# passive_balancing.net
KiCad netlist of a schematic drawn in Altium Designer
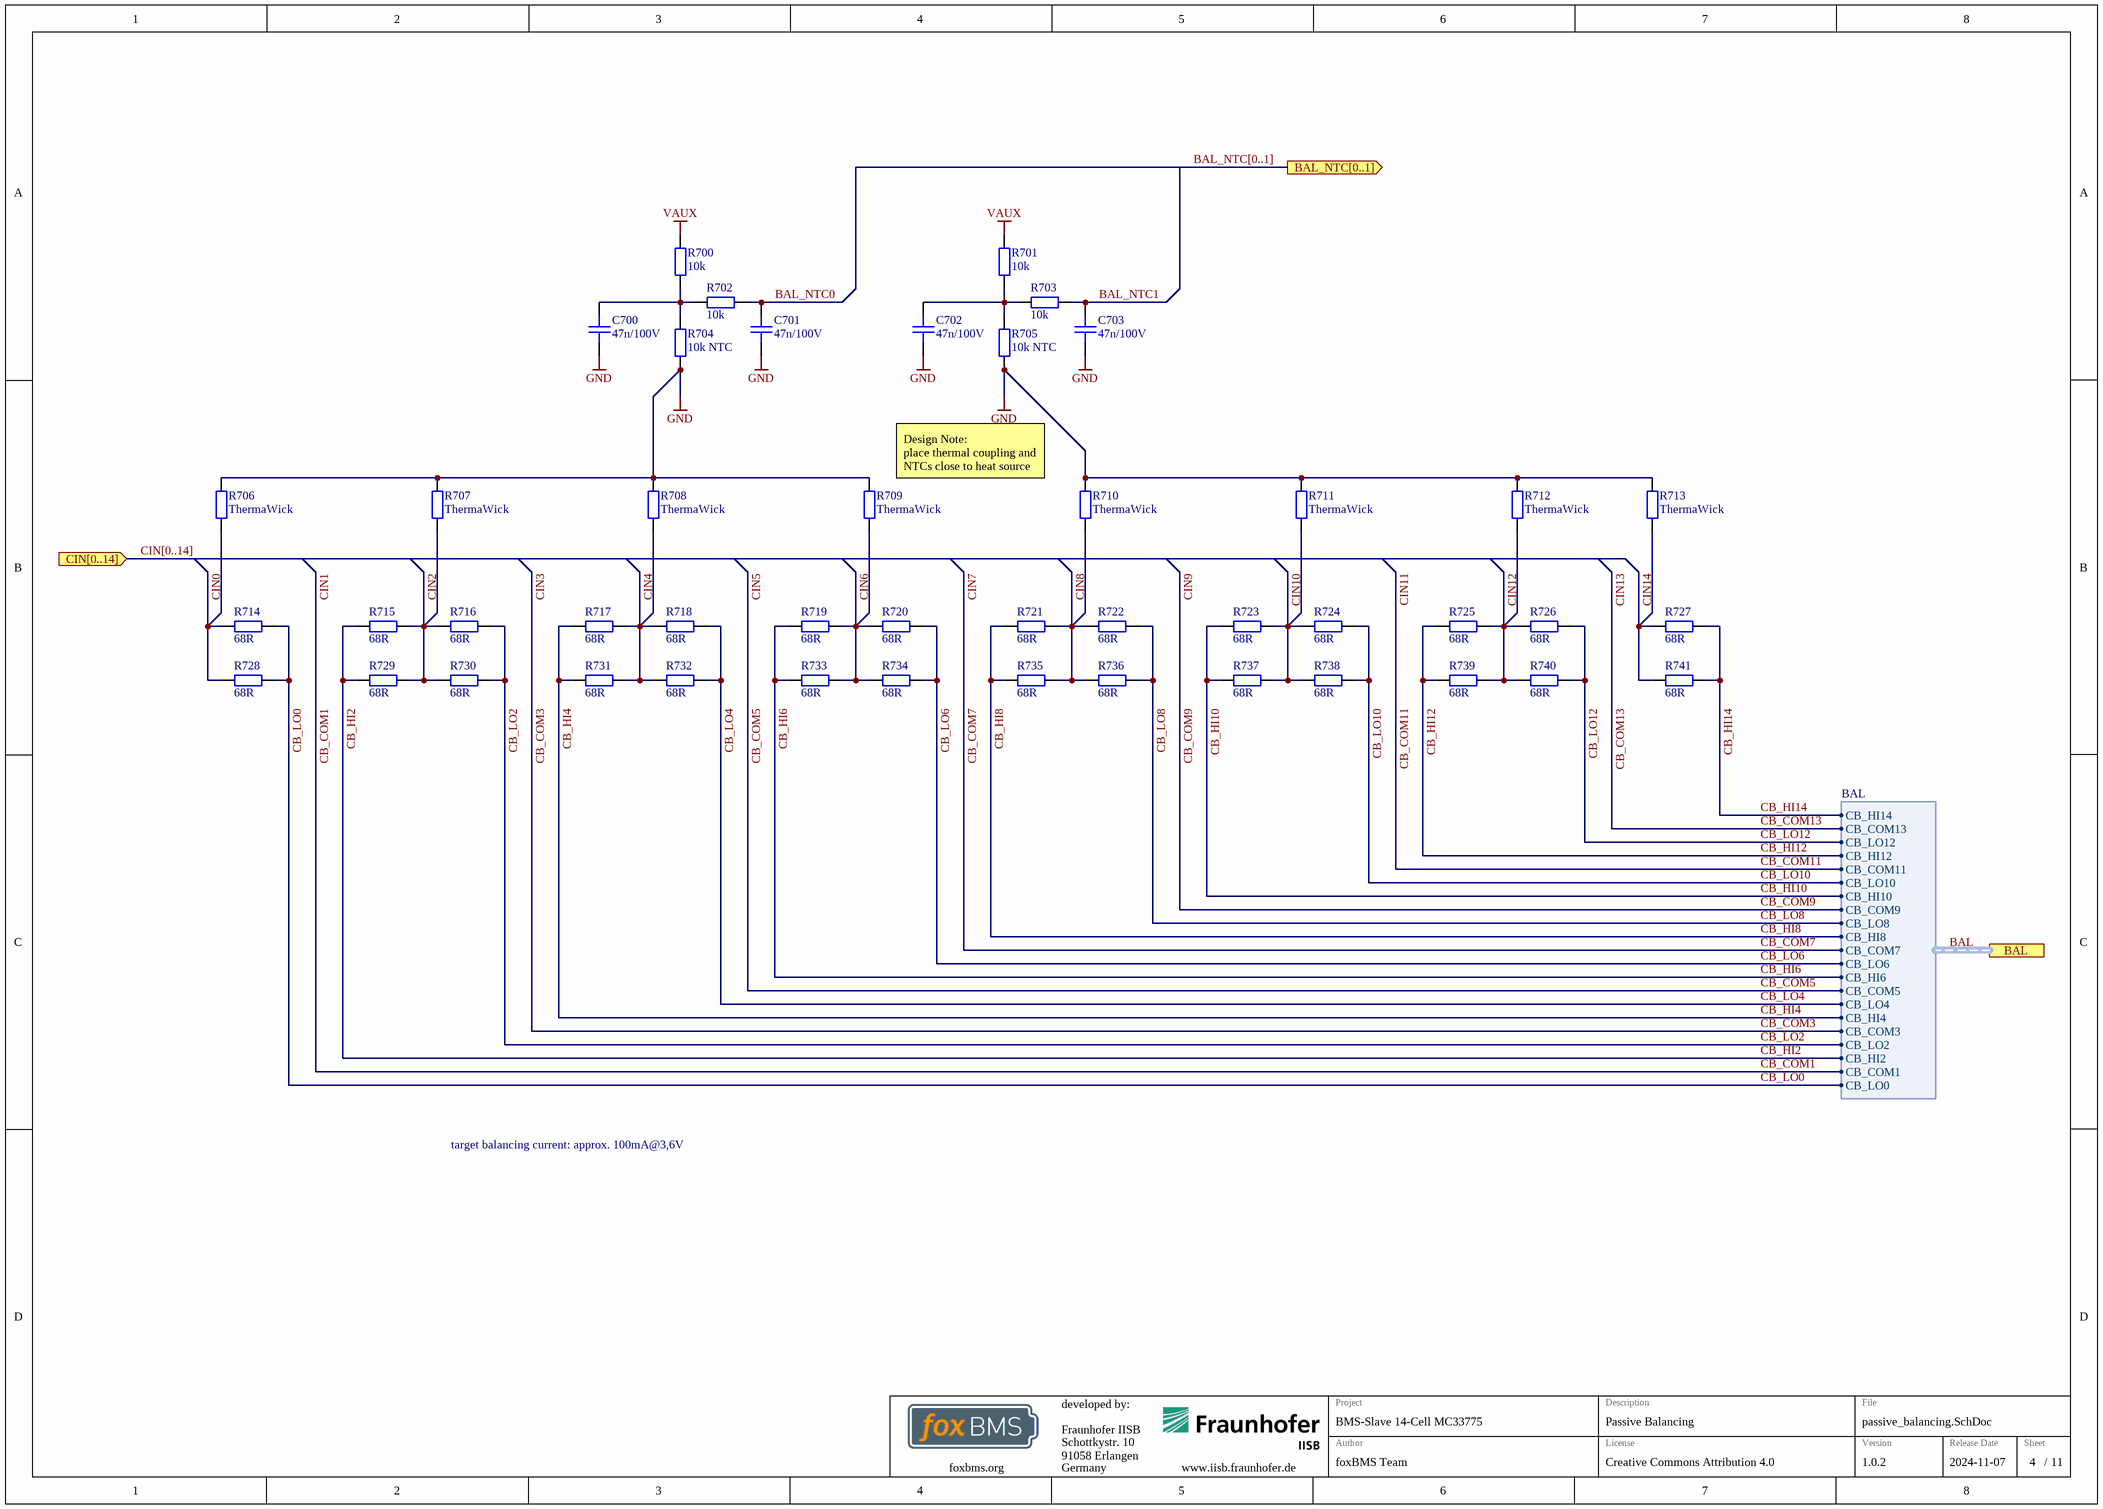
[diagram p0: passive_balancing.SchDoc]

(export (version "E")
  (design (tool "Eeschema 10.0.6"))
  (components
    (comp (ref "C700")
      (value "47n/100V")
      (footprint "CAPC1608X08N")
      (description "MLCC")
      (fields (field (name "PART NUMBER") "gen_C_ceramic_47n_100V_X7R_0603"))
      (libsource (lib "OE750") (part "C"))
    )
    (comp (ref "C701")
      (value "47n/100V")
      (footprint "CAPC1608X08N")
      (description "MLCC")
      (fields (field (name "PART NUMBER") "gen_C_ceramic_47n_100V_X7R_0603"))
      (libsource (lib "OE750") (part "C"))
    )
    (comp (ref "C702")
      (value "47n/100V")
      (footprint "CAPC1608X08N")
      (description "MLCC")
      (fields (field (name "PART NUMBER") "gen_C_ceramic_47n_100V_X7R_0603"))
      (libsource (lib "OE750") (part "C"))
    )
    (comp (ref "C703")
      (value "47n/100V")
      (footprint "CAPC1608X08N")
      (description "MLCC")
      (fields (field (name "PART NUMBER") "gen_C_ceramic_47n_100V_X7R_0603"))
      (libsource (lib "OE750") (part "C"))
    )
    (comp (ref "R700")
      (value "10k")
      (footprint "RESC1608X05N")
      (description "SMD Resistor 10k 0603")
      (fields (field (name "PART NUMBER") "gen_R_10k_0603") (field (name "TOLERANCE") "1%"))
      (libsource (lib "OE750") (part "R"))
    )
    (comp (ref "R701")
      (value "10k")
      (footprint "RESC1608X05N")
      (description "SMD Resistor 10k 0603")
      (fields (field (name "PART NUMBER") "gen_R_10k_0603") (field (name "TOLERANCE") "1%"))
      (libsource (lib "OE750") (part "R"))
    )
    (comp (ref "R702")
      (value "10k")
      (footprint "RESC1608X05N")
      (description "SMD Resistor 10k 0603")
      (fields (field (name "PART NUMBER") "gen_R_10k_0603") (field (name "TOLERANCE") "1%"))
      (libsource (lib "OE750") (part "R"))
    )
    (comp (ref "R703")
      (value "10k")
      (footprint "RESC1608X05N")
      (description "SMD Resistor 10k 0603")
      (fields (field (name "PART NUMBER") "gen_R_10k_0603") (field (name "TOLERANCE") "1%"))
      (libsource (lib "OE750") (part "R"))
    )
    (comp (ref "R704")
      (value "10k NTC")
      (footprint "RESC1005X04N")
      (description "SMD Resistor 10k NTC 0402")
      (fields (field (name "PART NUMBER") "gen_R_10k_NTC_0402") (field (name "POWER") "0.150W"))
      (libsource (lib "OE750") (part "R"))
    )
    (comp (ref "R705")
      (value "10k NTC")
      (footprint "RESC1005X04N")
      (description "SMD Resistor 10k NTC 0402")
      (fields (field (name "PART NUMBER") "gen_R_10k_NTC_0402") (field (name "POWER") "0.150W"))
      (libsource (lib "OE750") (part "R"))
    )
    (comp (ref "R706")
      (value "ThermaWick")
      (footprint "Vishay_THJP_0603")
      (description "ThermaWick thermal coupling 0603")
      (fields (field (name "PART NUMBER") "Vishay_THJP_0603"))
      (libsource (lib "OE750") (part "R"))
    )
    (comp (ref "R707")
      (value "ThermaWick")
      (footprint "Vishay_THJP_0603")
      (description "ThermaWick thermal coupling 0603")
      (fields (field (name "PART NUMBER") "Vishay_THJP_0603"))
      (libsource (lib "OE750") (part "R"))
    )
    (comp (ref "R708")
      (value "ThermaWick")
      (footprint "Vishay_THJP_0603")
      (description "ThermaWick thermal coupling 0603")
      (fields (field (name "PART NUMBER") "Vishay_THJP_0603"))
      (libsource (lib "OE750") (part "R"))
    )
    (comp (ref "R709")
      (value "ThermaWick")
      (footprint "Vishay_THJP_0603")
      (description "ThermaWick thermal coupling 0603")
      (fields (field (name "PART NUMBER") "Vishay_THJP_0603"))
      (libsource (lib "OE750") (part "R"))
    )
    (comp (ref "R710")
      (value "ThermaWick")
      (footprint "Vishay_THJP_0603")
      (description "ThermaWick thermal coupling 0603")
      (fields (field (name "PART NUMBER") "Vishay_THJP_0603"))
      (libsource (lib "OE750") (part "R"))
    )
    (comp (ref "R711")
      (value "ThermaWick")
      (footprint "Vishay_THJP_0603")
      (description "ThermaWick thermal coupling 0603")
      (fields (field (name "PART NUMBER") "Vishay_THJP_0603"))
      (libsource (lib "OE750") (part "R"))
    )
    (comp (ref "R712")
      (value "ThermaWick")
      (footprint "Vishay_THJP_0603")
      (description "ThermaWick thermal coupling 0603")
      (fields (field (name "PART NUMBER") "Vishay_THJP_0603"))
      (libsource (lib "OE750") (part "R"))
    )
    (comp (ref "R713")
      (value "ThermaWick")
      (footprint "Vishay_THJP_0603")
      (description "ThermaWick thermal coupling 0603")
      (fields (field (name "PART NUMBER") "Vishay_THJP_0603"))
      (libsource (lib "OE750") (part "R"))
    )
    (comp (ref "R714")
      (value "68R")
      (footprint "RESC5025X07N")
      (description "SMD Resistor 68R 2010")
      (fields (field (name "PART NUMBER") "gen_R_68R_2010") (field (name "TOLERANCE") "1%"))
      (libsource (lib "OE750") (part "R"))
    )
    (comp (ref "R715")
      (value "68R")
      (footprint "RESC5025X07N")
      (description "SMD Resistor 68R 2010")
      (fields (field (name "PART NUMBER") "gen_R_68R_2010") (field (name "TOLERANCE") "1%"))
      (libsource (lib "OE750") (part "R"))
    )
    (comp (ref "R716")
      (value "68R")
      (footprint "RESC5025X07N")
      (description "SMD Resistor 68R 2010")
      (fields (field (name "PART NUMBER") "gen_R_68R_2010") (field (name "TOLERANCE") "1%"))
      (libsource (lib "OE750") (part "R"))
    )
    (comp (ref "R717")
      (value "68R")
      (footprint "RESC5025X07N")
      (description "SMD Resistor 68R 2010")
      (fields (field (name "PART NUMBER") "gen_R_68R_2010") (field (name "TOLERANCE") "1%"))
      (libsource (lib "OE750") (part "R"))
    )
    (comp (ref "R718")
      (value "68R")
      (footprint "RESC5025X07N")
      (description "SMD Resistor 68R 2010")
      (fields (field (name "PART NUMBER") "gen_R_68R_2010") (field (name "TOLERANCE") "1%"))
      (libsource (lib "OE750") (part "R"))
    )
    (comp (ref "R719")
      (value "68R")
      (footprint "RESC5025X07N")
      (description "SMD Resistor 68R 2010")
      (fields (field (name "PART NUMBER") "gen_R_68R_2010") (field (name "TOLERANCE") "1%"))
      (libsource (lib "OE750") (part "R"))
    )
    (comp (ref "R720")
      (value "68R")
      (footprint "RESC5025X07N")
      (description "SMD Resistor 68R 2010")
      (fields (field (name "PART NUMBER") "gen_R_68R_2010") (field (name "TOLERANCE") "1%"))
      (libsource (lib "OE750") (part "R"))
    )
    (comp (ref "R721")
      (value "68R")
      (footprint "RESC5025X07N")
      (description "SMD Resistor 68R 2010")
      (fields (field (name "PART NUMBER") "gen_R_68R_2010") (field (name "TOLERANCE") "1%"))
      (libsource (lib "OE750") (part "R"))
    )
    (comp (ref "R722")
      (value "68R")
      (footprint "RESC5025X07N")
      (description "SMD Resistor 68R 2010")
      (fields (field (name "PART NUMBER") "gen_R_68R_2010") (field (name "TOLERANCE") "1%"))
      (libsource (lib "OE750") (part "R"))
    )
    (comp (ref "R723")
      (value "68R")
      (footprint "RESC5025X07N")
      (description "SMD Resistor 68R 2010")
      (fields (field (name "PART NUMBER") "gen_R_68R_2010") (field (name "TOLERANCE") "1%"))
      (libsource (lib "OE750") (part "R"))
    )
    (comp (ref "R724")
      (value "68R")
      (footprint "RESC5025X07N")
      (description "SMD Resistor 68R 2010")
      (fields (field (name "PART NUMBER") "gen_R_68R_2010") (field (name "TOLERANCE") "1%"))
      (libsource (lib "OE750") (part "R"))
    )
    (comp (ref "R725")
      (value "68R")
      (footprint "RESC5025X07N")
      (description "SMD Resistor 68R 2010")
      (fields (field (name "PART NUMBER") "gen_R_68R_2010") (field (name "TOLERANCE") "1%"))
      (libsource (lib "OE750") (part "R"))
    )
    (comp (ref "R726")
      (value "68R")
      (footprint "RESC5025X07N")
      (description "SMD Resistor 68R 2010")
      (fields (field (name "PART NUMBER") "gen_R_68R_2010") (field (name "TOLERANCE") "1%"))
      (libsource (lib "OE750") (part "R"))
    )
    (comp (ref "R727")
      (value "68R")
      (footprint "RESC5025X07N")
      (description "SMD Resistor 68R 2010")
      (fields (field (name "PART NUMBER") "gen_R_68R_2010") (field (name "TOLERANCE") "1%"))
      (libsource (lib "OE750") (part "R"))
    )
    (comp (ref "R728")
      (value "68R")
      (footprint "RESC5025X07N")
      (description "SMD Resistor 68R 2010")
      (fields (field (name "PART NUMBER") "gen_R_68R_2010") (field (name "TOLERANCE") "1%"))
      (libsource (lib "OE750") (part "R"))
    )
    (comp (ref "R729")
      (value "68R")
      (footprint "RESC5025X07N")
      (description "SMD Resistor 68R 2010")
      (fields (field (name "PART NUMBER") "gen_R_68R_2010") (field (name "TOLERANCE") "1%"))
      (libsource (lib "OE750") (part "R"))
    )
    (comp (ref "R730")
      (value "68R")
      (footprint "RESC5025X07N")
      (description "SMD Resistor 68R 2010")
      (fields (field (name "PART NUMBER") "gen_R_68R_2010") (field (name "TOLERANCE") "1%"))
      (libsource (lib "OE750") (part "R"))
    )
    (comp (ref "R731")
      (value "68R")
      (footprint "RESC5025X07N")
      (description "SMD Resistor 68R 2010")
      (fields (field (name "PART NUMBER") "gen_R_68R_2010") (field (name "TOLERANCE") "1%"))
      (libsource (lib "OE750") (part "R"))
    )
    (comp (ref "R732")
      (value "68R")
      (footprint "RESC5025X07N")
      (description "SMD Resistor 68R 2010")
      (fields (field (name "PART NUMBER") "gen_R_68R_2010") (field (name "TOLERANCE") "1%"))
      (libsource (lib "OE750") (part "R"))
    )
    (comp (ref "R733")
      (value "68R")
      (footprint "RESC5025X07N")
      (description "SMD Resistor 68R 2010")
      (fields (field (name "PART NUMBER") "gen_R_68R_2010") (field (name "TOLERANCE") "1%"))
      (libsource (lib "OE750") (part "R"))
    )
    (comp (ref "R734")
      (value "68R")
      (footprint "RESC5025X07N")
      (description "SMD Resistor 68R 2010")
      (fields (field (name "PART NUMBER") "gen_R_68R_2010") (field (name "TOLERANCE") "1%"))
      (libsource (lib "OE750") (part "R"))
    )
    (comp (ref "R735")
      (value "68R")
      (footprint "RESC5025X07N")
      (description "SMD Resistor 68R 2010")
      (fields (field (name "PART NUMBER") "gen_R_68R_2010") (field (name "TOLERANCE") "1%"))
      (libsource (lib "OE750") (part "R"))
    )
    (comp (ref "R736")
      (value "68R")
      (footprint "RESC5025X07N")
      (description "SMD Resistor 68R 2010")
      (fields (field (name "PART NUMBER") "gen_R_68R_2010") (field (name "TOLERANCE") "1%"))
      (libsource (lib "OE750") (part "R"))
    )
    (comp (ref "R737")
      (value "68R")
      (footprint "RESC5025X07N")
      (description "SMD Resistor 68R 2010")
      (fields (field (name "PART NUMBER") "gen_R_68R_2010") (field (name "TOLERANCE") "1%"))
      (libsource (lib "OE750") (part "R"))
    )
    (comp (ref "R738")
      (value "68R")
      (footprint "RESC5025X07N")
      (description "SMD Resistor 68R 2010")
      (fields (field (name "PART NUMBER") "gen_R_68R_2010") (field (name "TOLERANCE") "1%"))
      (libsource (lib "OE750") (part "R"))
    )
    (comp (ref "R739")
      (value "68R")
      (footprint "RESC5025X07N")
      (description "SMD Resistor 68R 2010")
      (fields (field (name "PART NUMBER") "gen_R_68R_2010") (field (name "TOLERANCE") "1%"))
      (libsource (lib "OE750") (part "R"))
    )
    (comp (ref "R740")
      (value "68R")
      (footprint "RESC5025X07N")
      (description "SMD Resistor 68R 2010")
      (fields (field (name "PART NUMBER") "gen_R_68R_2010") (field (name "TOLERANCE") "1%"))
      (libsource (lib "OE750") (part "R"))
    )
    (comp (ref "R741")
      (value "68R")
      (footprint "RESC5025X07N")
      (description "SMD Resistor 68R 2010")
      (fields (field (name "PART NUMBER") "gen_R_68R_2010") (field (name "TOLERANCE") "1%"))
      (libsource (lib "OE750") (part "R"))
    )
  )
  (nets
    (net (code "2") (name "/BAL_NTC0") (class "Default")
      (node (ref "C701") (pin "2") (pinfunction "2_2") (pintype "passive"))
      (node (ref "R702") (pin "1") (pinfunction "1_1") (pintype "passive"))
    )
    (net (code "3") (name "/BAL_NTC1") (class "Default")
      (node (ref "C703") (pin "2") (pinfunction "2_2") (pintype "passive"))
      (node (ref "R703") (pin "1") (pinfunction "1_1") (pintype "passive"))
    )
    (net (code "6") (name "/CB_HI2") (class "Default")
      (node (ref "R715") (pin "2") (pinfunction "2_2") (pintype "passive"))
      (node (ref "R729") (pin "2") (pinfunction "2_2") (pintype "passive"))
    )
    (net (code "7") (name "/CB_HI4") (class "Default")
      (node (ref "R717") (pin "2") (pinfunction "2_2") (pintype "passive"))
      (node (ref "R731") (pin "2") (pinfunction "2_2") (pintype "passive"))
    )
    (net (code "8") (name "/CB_HI6") (class "Default")
      (node (ref "R719") (pin "2") (pinfunction "2_2") (pintype "passive"))
      (node (ref "R733") (pin "2") (pinfunction "2_2") (pintype "passive"))
    )
    (net (code "9") (name "/CB_HI8") (class "Default")
      (node (ref "R721") (pin "2") (pinfunction "2_2") (pintype "passive"))
      (node (ref "R735") (pin "2") (pinfunction "2_2") (pintype "passive"))
    )
    (net (code "10") (name "/CB_HI10") (class "Default")
      (node (ref "R723") (pin "2") (pinfunction "2_2") (pintype "passive"))
      (node (ref "R737") (pin "2") (pinfunction "2_2") (pintype "passive"))
    )
    (net (code "11") (name "/CB_HI12") (class "Default")
      (node (ref "R725") (pin "2") (pinfunction "2_2") (pintype "passive"))
      (node (ref "R739") (pin "2") (pinfunction "2_2") (pintype "passive"))
    )
    (net (code "12") (name "/CB_HI14") (class "Default")
      (node (ref "R727") (pin "1") (pinfunction "1_1") (pintype "passive"))
      (node (ref "R741") (pin "1") (pinfunction "1_1") (pintype "passive"))
    )
    (net (code "13") (name "/CB_LO0") (class "Default")
      (node (ref "R714") (pin "1") (pinfunction "1_1") (pintype "passive"))
      (node (ref "R728") (pin "1") (pinfunction "1_1") (pintype "passive"))
    )
    (net (code "14") (name "/CB_LO2") (class "Default")
      (node (ref "R716") (pin "1") (pinfunction "1_1") (pintype "passive"))
      (node (ref "R730") (pin "1") (pinfunction "1_1") (pintype "passive"))
    )
    (net (code "15") (name "/CB_LO4") (class "Default")
      (node (ref "R718") (pin "1") (pinfunction "1_1") (pintype "passive"))
      (node (ref "R732") (pin "1") (pinfunction "1_1") (pintype "passive"))
    )
    (net (code "16") (name "/CB_LO6") (class "Default")
      (node (ref "R720") (pin "1") (pinfunction "1_1") (pintype "passive"))
      (node (ref "R734") (pin "1") (pinfunction "1_1") (pintype "passive"))
    )
    (net (code "17") (name "/CB_LO8") (class "Default")
      (node (ref "R722") (pin "1") (pinfunction "1_1") (pintype "passive"))
      (node (ref "R736") (pin "1") (pinfunction "1_1") (pintype "passive"))
    )
    (net (code "18") (name "/CB_LO10") (class "Default")
      (node (ref "R724") (pin "1") (pinfunction "1_1") (pintype "passive"))
      (node (ref "R738") (pin "1") (pinfunction "1_1") (pintype "passive"))
    )
    (net (code "19") (name "/CB_LO12") (class "Default")
      (node (ref "R726") (pin "1") (pinfunction "1_1") (pintype "passive"))
      (node (ref "R740") (pin "1") (pinfunction "1_1") (pintype "passive"))
    )
    (net (code "20") (name "/CIN0") (class "Default")
      (node (ref "R706") (pin "1") (pinfunction "1_1") (pintype "passive"))
      (node (ref "R714") (pin "2") (pinfunction "2_2") (pintype "passive"))
      (node (ref "R728") (pin "2") (pinfunction "2_2") (pintype "passive"))
    )
    (net (code "22") (name "/CIN2") (class "Default")
      (node (ref "R707") (pin "1") (pinfunction "1_1") (pintype "passive"))
      (node (ref "R715") (pin "1") (pinfunction "1_1") (pintype "passive"))
      (node (ref "R716") (pin "2") (pinfunction "2_2") (pintype "passive"))
      (node (ref "R729") (pin "1") (pinfunction "1_1") (pintype "passive"))
      (node (ref "R730") (pin "2") (pinfunction "2_2") (pintype "passive"))
    )
    (net (code "24") (name "/CIN4") (class "Default")
      (node (ref "R708") (pin "1") (pinfunction "1_1") (pintype "passive"))
      (node (ref "R717") (pin "1") (pinfunction "1_1") (pintype "passive"))
      (node (ref "R718") (pin "2") (pinfunction "2_2") (pintype "passive"))
      (node (ref "R731") (pin "1") (pinfunction "1_1") (pintype "passive"))
      (node (ref "R732") (pin "2") (pinfunction "2_2") (pintype "passive"))
    )
    (net (code "26") (name "/CIN6") (class "Default")
      (node (ref "R709") (pin "1") (pinfunction "1_1") (pintype "passive"))
      (node (ref "R719") (pin "1") (pinfunction "1_1") (pintype "passive"))
      (node (ref "R720") (pin "2") (pinfunction "2_2") (pintype "passive"))
      (node (ref "R733") (pin "1") (pinfunction "1_1") (pintype "passive"))
      (node (ref "R734") (pin "2") (pinfunction "2_2") (pintype "passive"))
    )
    (net (code "28") (name "/CIN8") (class "Default")
      (node (ref "R710") (pin "1") (pinfunction "1_1") (pintype "passive"))
      (node (ref "R721") (pin "1") (pinfunction "1_1") (pintype "passive"))
      (node (ref "R722") (pin "2") (pinfunction "2_2") (pintype "passive"))
      (node (ref "R735") (pin "1") (pinfunction "1_1") (pintype "passive"))
      (node (ref "R736") (pin "2") (pinfunction "2_2") (pintype "passive"))
    )
    (net (code "30") (name "/CIN10") (class "Default")
      (node (ref "R711") (pin "1") (pinfunction "1_1") (pintype "passive"))
      (node (ref "R723") (pin "1") (pinfunction "1_1") (pintype "passive"))
      (node (ref "R724") (pin "2") (pinfunction "2_2") (pintype "passive"))
      (node (ref "R737") (pin "1") (pinfunction "1_1") (pintype "passive"))
      (node (ref "R738") (pin "2") (pinfunction "2_2") (pintype "passive"))
    )
    (net (code "32") (name "/CIN12") (class "Default")
      (node (ref "R712") (pin "1") (pinfunction "1_1") (pintype "passive"))
      (node (ref "R725") (pin "1") (pinfunction "1_1") (pintype "passive"))
      (node (ref "R726") (pin "2") (pinfunction "2_2") (pintype "passive"))
      (node (ref "R739") (pin "1") (pinfunction "1_1") (pintype "passive"))
      (node (ref "R740") (pin "2") (pinfunction "2_2") (pintype "passive"))
    )
    (net (code "34") (name "/CIN14") (class "Default")
      (node (ref "R713") (pin "1") (pinfunction "1_1") (pintype "passive"))
      (node (ref "R727") (pin "2") (pinfunction "2_2") (pintype "passive"))
      (node (ref "R741") (pin "2") (pinfunction "2_2") (pintype "passive"))
    )
    (net (code "36") (name "GND") (class "Default")
      (node (ref "C700") (pin "1") (pinfunction "1_1") (pintype "passive"))
      (node (ref "C701") (pin "1") (pinfunction "1_1") (pintype "passive"))
      (node (ref "C702") (pin "1") (pinfunction "1_1") (pintype "passive"))
      (node (ref "C703") (pin "1") (pinfunction "1_1") (pintype "passive"))
      (node (ref "R704") (pin "2") (pinfunction "2_2") (pintype "passive"))
      (node (ref "R705") (pin "2") (pinfunction "2_2") (pintype "passive"))
      (node (ref "R706") (pin "2") (pinfunction "2_2") (pintype "passive"))
      (node (ref "R707") (pin "2") (pinfunction "2_2") (pintype "passive"))
      (node (ref "R708") (pin "2") (pinfunction "2_2") (pintype "passive"))
      (node (ref "R709") (pin "2") (pinfunction "2_2") (pintype "passive"))
      (node (ref "R710") (pin "2") (pinfunction "2_2") (pintype "passive"))
      (node (ref "R711") (pin "2") (pinfunction "2_2") (pintype "passive"))
      (node (ref "R712") (pin "2") (pinfunction "2_2") (pintype "passive"))
      (node (ref "R713") (pin "2") (pinfunction "2_2") (pintype "passive"))
    )
    (net (code "37") (name "Net-(C700-Pad2)") (class "Default")
      (node (ref "C700") (pin "2") (pinfunction "2_2") (pintype "passive"))
      (node (ref "R700") (pin "1") (pinfunction "1_1") (pintype "passive"))
      (node (ref "R702") (pin "2") (pinfunction "2_2") (pintype "passive"))
      (node (ref "R704") (pin "1") (pinfunction "1_1") (pintype "passive"))
    )
    (net (code "38") (name "Net-(C702-Pad2)") (class "Default")
      (node (ref "C702") (pin "2") (pinfunction "2_2") (pintype "passive"))
      (node (ref "R701") (pin "1") (pinfunction "1_1") (pintype "passive"))
      (node (ref "R703") (pin "2") (pinfunction "2_2") (pintype "passive"))
      (node (ref "R705") (pin "1") (pinfunction "1_1") (pintype "passive"))
    )
    (net (code "39") (name "VAUX") (class "Default")
      (node (ref "R700") (pin "2") (pinfunction "2_2") (pintype "passive"))
      (node (ref "R701") (pin "2") (pinfunction "2_2") (pintype "passive"))
    )
  )
)
